# ch347f.net
KiCad netlist of a schematic drawn in Altium Designer
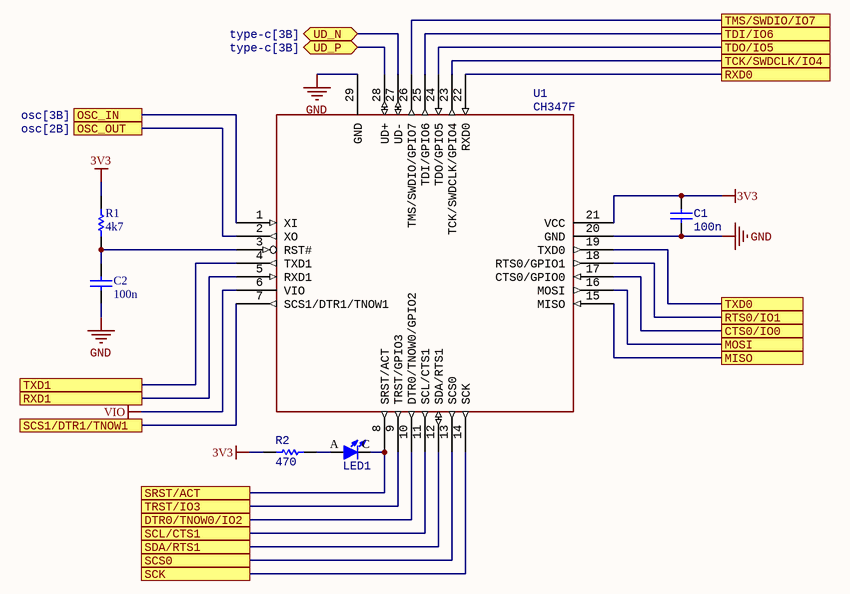
[diagram p0: ch347f.SchDoc]

(export (version "E")
  (design (tool "Eeschema 10.0.6"))
  (components
    (comp (ref "C1")
      (value "100n")
      (footprint "footprints:CAPC100X50X55L25N")
      (fields
        (field (name "MPN") "TCC0402X5R104M250AT")
        (field (name "MANUFACTURER") "CCTC(三环)")
        (field (name "Comment") "Capacitor")
      )
      (libsource (lib "std_lib") (part "Capacitor"))
    )
    (comp (ref "C2")
      (value "100n")
      (footprint "footprints:CAPC100X50X55L25N")
      (fields
        (field (name "MPN") "TCC0402X5R104M250AT")
        (field (name "MANUFACTURER") "CCTC(三环)")
        (field (name "Comment") "Capacitor")
      )
      (libsource (lib "std_lib") (part "Capacitor"))
    )
    (comp (ref "LED1")
      (value "蓝灯 正贴")
      (footprint "footprints:LEDC100X50X45L25N")
      (description "贴片LED")
      (libsource (lib "mcontroller") (part "LED-SMD"))
    )
    (comp (ref "R1")
      (value "4k7")
      (footprint "footprints:RESC100X50X35L25N")
      (fields
        (field (name "MPN") "RTT02472JTH")
        (field (name "MANUFACTURER") "RALEC(旺诠)")
        (field (name "Comment") "Resistor")
      )
      (libsource (lib "std_lib") (part "Resistor"))
    )
    (comp (ref "R2")
      (value "470")
      (footprint "footprints:RESC100X50X35L25N")
      (fields
        (field (name "MPN") "RTT02471JTH")
        (field (name "MANUFACTURER") "RALEC(旺诠)")
        (field (name "Comment") "Resistor")
      )
      (libsource (lib "std_lib") (part "Resistor"))
    )
    (comp (ref "U1")
      (value "CH347F")
      (footprint "QFN28_4X4")
      (description "High Speed USB to UART + SPI + IIC + JTAG")
      (libsource (lib "Sch") (part "CH347F"))
    )
  )
  (nets
    (net (code "1") (name "/CTS0{slash}IO0") (class "Default")
      (node (ref "U1") (pin "17") (pinfunction "CTS0/GPIO0_17") (pintype "input"))
    )
    (net (code "2") (name "/DTR0{slash}TNOW0{slash}IO2") (class "Default")
      (node (ref "U1") (pin "10") (pinfunction "DTR0/TNOW0/GPIO2_10") (pintype "output"))
    )
    (net (code "3") (name "/MISO") (class "Default")
      (node (ref "U1") (pin "15") (pinfunction "MISO_15") (pintype "input"))
    )
    (net (code "4") (name "/MOSI") (class "Default")
      (node (ref "U1") (pin "16") (pinfunction "MOSI_16") (pintype "output"))
    )
    (net (code "5") (name "/OSC_IN") (class "Default")
      (node (ref "U1") (pin "1") (pinfunction "XI_1") (pintype "input"))
    )
    (net (code "6") (name "/OSC_OUT") (class "Default")
      (node (ref "U1") (pin "2") (pinfunction "XO_2") (pintype "output"))
    )
    (net (code "7") (name "/RTS0{slash}IO1") (class "Default")
      (node (ref "U1") (pin "18") (pinfunction "RTS0/GPIO1_18") (pintype "output"))
    )
    (net (code "8") (name "/RXD0") (class "Default")
      (node (ref "U1") (pin "22") (pinfunction "RXD0_22") (pintype "input"))
    )
    (net (code "9") (name "/RXD1") (class "Default")
      (node (ref "U1") (pin "5") (pinfunction "RXD1_5") (pintype "input"))
    )
    (net (code "10") (name "/SCK") (class "Default")
      (node (ref "U1") (pin "14") (pinfunction "SCK_14") (pintype "output"))
    )
    (net (code "11") (name "/SCL{slash}CTS1") (class "Default")
      (node (ref "U1") (pin "11") (pinfunction "SCL/CTS1_11") (pintype "output"))
    )
    (net (code "12") (name "/SCS0") (class "Default")
      (node (ref "U1") (pin "13") (pinfunction "SCS0_13") (pintype "output"))
    )
    (net (code "13") (name "/SCS1{slash}DTR1{slash}TNOW1") (class "Default")
      (node (ref "U1") (pin "7") (pinfunction "SCS1/DTR1/TNOW1_7") (pintype "output"))
    )
    (net (code "14") (name "/SDA{slash}RTS1") (class "Default")
      (node (ref "U1") (pin "12") (pinfunction "SDA/RTS1_12") (pintype "bidirectional"))
    )
    (net (code "15") (name "/SRST{slash}ACT") (class "Default")
      (node (ref "LED1") (pin "C") (pinfunction "K_C") (pintype "passive"))
      (node (ref "U1") (pin "8") (pinfunction "SRST/ACT_8") (pintype "output"))
    )
    (net (code "16") (name "/TCK{slash}SWDCLK{slash}IO4") (class "Default")
      (node (ref "U1") (pin "23") (pinfunction "TCK/SWDCLK/GPIO4_23") (pintype "output"))
    )
    (net (code "17") (name "/TDI{slash}IO6") (class "Default")
      (node (ref "U1") (pin "25") (pinfunction "TDI/GPIO6_25") (pintype "output"))
    )
    (net (code "18") (name "/TDO{slash}IO5") (class "Default")
      (node (ref "U1") (pin "24") (pinfunction "TDO/GPIO5_24") (pintype "input"))
    )
    (net (code "19") (name "/TMS{slash}SWDIO{slash}IO7") (class "Default")
      (node (ref "U1") (pin "26") (pinfunction "TMS/SWDIO/GPIO7_26") (pintype "output"))
    )
    (net (code "20") (name "/TRST{slash}IO3") (class "Default")
      (node (ref "U1") (pin "9") (pinfunction "TRST/GPIO3_9") (pintype "output"))
    )
    (net (code "21") (name "/TXD0") (class "Default")
      (node (ref "U1") (pin "19") (pinfunction "TXD0_19") (pintype "output"))
    )
    (net (code "22") (name "/TXD1") (class "Default")
      (node (ref "U1") (pin "4") (pinfunction "TXD1_4") (pintype "output"))
    )
    (net (code "23") (name "/UD_N") (class "Default")
      (node (ref "U1") (pin "27") (pinfunction "UD-_27") (pintype "bidirectional"))
    )
    (net (code "24") (name "/UD_P") (class "Default")
      (node (ref "U1") (pin "28") (pinfunction "UD+_28") (pintype "bidirectional"))
    )
    (net (code "25") (name "3V3") (class "Default")
      (node (ref "C1") (pin "2") (pinfunction "2_2") (pintype "passive"))
      (node (ref "R1") (pin "1") (pinfunction "1_1") (pintype "passive"))
      (node (ref "R2") (pin "1") (pinfunction "1_1") (pintype "passive"))
      (node (ref "U1") (pin "21") (pinfunction "VCC_21") (pintype "power_in"))
    )
    (net (code "26") (name "GND") (class "Default")
      (node (ref "C1") (pin "1") (pinfunction "1_1") (pintype "passive"))
      (node (ref "C2") (pin "1") (pinfunction "1_1") (pintype "passive"))
      (node (ref "U1") (pin "20") (pinfunction "GND_20") (pintype "power_in"))
      (node (ref "U1") (pin "29") (pinfunction "GND_29") (pintype "power_in"))
    )
    (net (code "27") (name "Net-(LED1-PadA)") (class "Default")
      (node (ref "LED1") (pin "A") (pinfunction "A_A") (pintype "passive"))
      (node (ref "R2") (pin "2") (pinfunction "2_2") (pintype "passive"))
    )
    (net (code "28") (name "Net-(U1-RST#)") (class "Default")
      (node (ref "C2") (pin "2") (pinfunction "2_2") (pintype "passive"))
      (node (ref "R1") (pin "2") (pinfunction "2_2") (pintype "passive"))
      (node (ref "U1") (pin "3") (pinfunction "RST#_3") (pintype "input"))
    )
    (net (code "29") (name "VIO") (class "Default")
      (node (ref "U1") (pin "6") (pinfunction "VIO_6") (pintype "power_in"))
    )
  )
)
